# NewGateway.net
KiCad netlist of a schematic drawn in Altium Designer
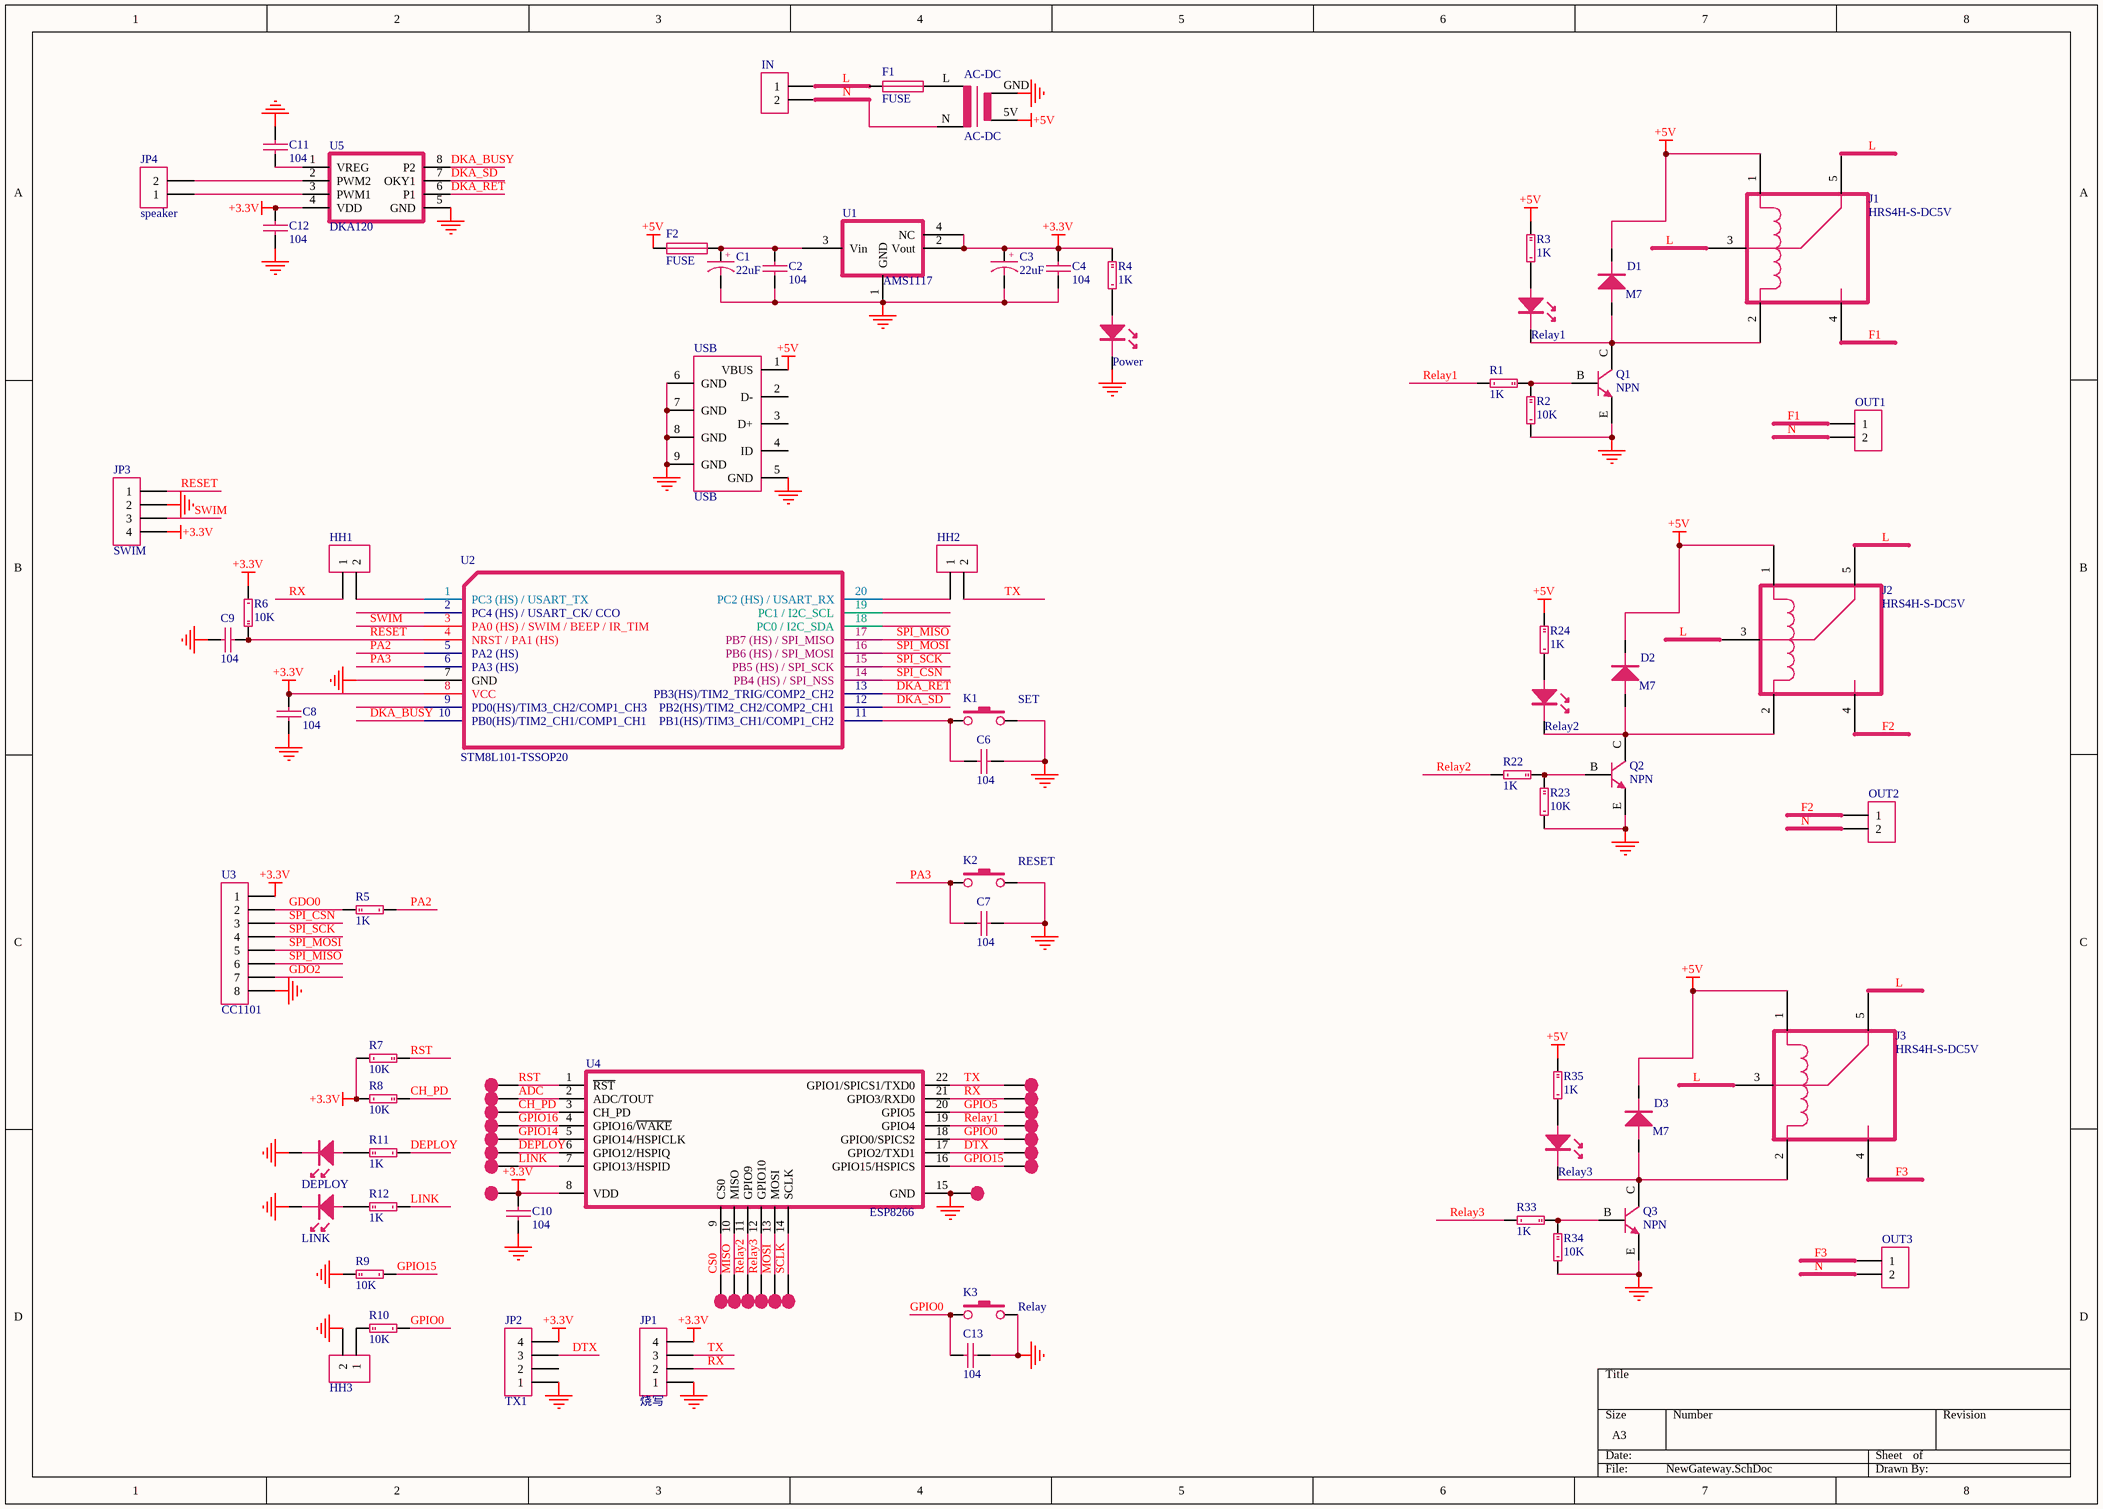
[diagram p0: NewGateway.SchDoc]

(export (version "E")
  (design (tool "Eeschema 10.0.6"))
  (components
    (comp (ref "AC-DC")
      (value "AC-DC")
      (footprint "AC-DC")
      (description "5V700mA(3.5W) 隔离开关电源模块/AC-DC降压模块")
      (libsource (lib "Sch_Lib") (part "AC-DC"))
    )
    (comp (ref "C1")
      (value "22uF")
      (footprint "C3528")
      (description "极性电容")
      (libsource (lib "Sch_Lib") (part "CAPACITOR"))
    )
    (comp (ref "C2")
      (value "104")
      (footprint "C0603")
      (description "无极性电容")
      (libsource (lib "Sch_Lib") (part "CAP"))
    )
    (comp (ref "C3")
      (value "22uF")
      (footprint "C3528")
      (description "极性电容")
      (libsource (lib "Sch_Lib") (part "CAPACITOR"))
    )
    (comp (ref "C4")
      (value "104")
      (footprint "C0603")
      (description "无极性电容")
      (libsource (lib "Sch_Lib") (part "CAP"))
    )
    (comp (ref "C6")
      (value "104")
      (footprint "C0603")
      (description "无极性电容")
      (libsource (lib "Sch_Lib") (part "CAP"))
    )
    (comp (ref "C7")
      (value "104")
      (footprint "C0603")
      (description "无极性电容")
      (libsource (lib "Sch_Lib") (part "CAP"))
    )
    (comp (ref "C8")
      (value "104")
      (footprint "C0603")
      (description "无极性电容")
      (libsource (lib "Sch_Lib") (part "CAP"))
    )
    (comp (ref "C9")
      (value "104")
      (footprint "C0603")
      (description "无极性电容")
      (libsource (lib "Sch_Lib") (part "CAP"))
    )
    (comp (ref "C10")
      (value "104")
      (footprint "C0603")
      (description "无极性电容")
      (libsource (lib "Sch_Lib") (part "CAP"))
    )
    (comp (ref "C11")
      (value "104")
      (footprint "C0603")
      (description "无极性电容")
      (libsource (lib "Sch_Lib") (part "CAP"))
    )
    (comp (ref "C12")
      (value "104")
      (footprint "C0603")
      (description "无极性电容")
      (libsource (lib "Sch_Lib") (part "CAP"))
    )
    (comp (ref "C13")
      (value "104")
      (footprint "C0603")
      (description "无极性电容")
      (libsource (lib "Sch_Lib") (part "CAP"))
    )
    (comp (ref "D1")
      (value "M7")
      (footprint "DO-214A")
      (description "二极管")
      (libsource (lib "Sch_Lib") (part "DIODE"))
    )
    (comp (ref "D2")
      (value "M7")
      (footprint "DO-214A")
      (description "二极管")
      (libsource (lib "Sch_Lib") (part "DIODE"))
    )
    (comp (ref "D3")
      (value "M7")
      (footprint "DO-214A")
      (description "二极管")
      (libsource (lib "Sch_Lib") (part "DIODE"))
    )
    (comp (ref "DEPLOY")
      (value "LED")
      (footprint "LED0603")
      (description "LED灯")
      (libsource (lib "Sch_Lib") (part "LED"))
    )
    (comp (ref "F1")
      (value "FUSE")
      (footprint "Fuse Holder")
      (description "保险丝")
      (libsource (lib "Sch_Lib") (part "FUSE"))
    )
    (comp (ref "F2")
      (value "FUSE")
      (footprint "F1208")
      (description "保险丝")
      (libsource (lib "Sch_Lib") (part "FUSE"))
    )
    (comp (ref "HH1")
      (value "~")
      (footprint "SIP2-2.54MM")
      (description "2P接插件")
      (libsource (lib "Sch_Lib") (part "HEADER 2X1"))
    )
    (comp (ref "HH2")
      (value "~")
      (footprint "SIP2-2.54MM")
      (description "2P接插件")
      (libsource (lib "Sch_Lib") (part "HEADER 2X1"))
    )
    (comp (ref "HH3")
      (value "~")
      (footprint "SIP2-2.54MM")
      (description "2P接插件")
      (libsource (lib "") (part "HEADER 2X1_1"))
    )
    (comp (ref "IN")
      (value "~")
      (footprint "2EDG_5.08_2P")
      (description "2P接插件")
      (libsource (lib "") (part "HEADER 2X1_1"))
    )
    (comp (ref "J1")
      (value "HRS4H-S-DC5V")
      (footprint "HRS4H")
      (description "HKE汇港继电器")
      (libsource (lib "Sch_Lib") (part "HRS4H-S-DC5V"))
    )
    (comp (ref "J2")
      (value "HRS4H-S-DC5V")
      (footprint "HRS4H")
      (description "HKE汇港继电器")
      (libsource (lib "Sch_Lib") (part "HRS4H-S-DC5V"))
    )
    (comp (ref "J3")
      (value "HRS4H-S-DC5V")
      (footprint "HRS4H")
      (description "HKE汇港继电器")
      (libsource (lib "Sch_Lib") (part "HRS4H-S-DC5V"))
    )
    (comp (ref "JP1")
      (value "烧写")
      (footprint "SIP4-2.54MM")
      (description "4P接插件")
      (libsource (lib "Sch_Lib") (part "HEADER 4X1"))
    )
    (comp (ref "JP2")
      (value "TX1")
      (footprint "SIP4-2.54MM")
      (description "4P接插件")
      (libsource (lib "Sch_Lib") (part "HEADER 4X1"))
    )
    (comp (ref "JP3")
      (value "SWIM")
      (footprint "SIP4-2.54MM")
      (description "4P接插件")
      (libsource (lib "") (part "HEADER 4X1_1"))
    )
    (comp (ref "JP4")
      (value "speaker")
      (footprint "SIP2-1.27MM")
      (description "2P接插件")
      (libsource (lib "") (part "HEADER 2X1_3"))
    )
    (comp (ref "K1")
      (value "SET")
      (footprint "SW-TACT-4.5MM")
      (description "按键")
      (libsource (lib "Sch_Lib") (part "SW-PB"))
    )
    (comp (ref "K2")
      (value "RESET")
      (footprint "SW-TACT-4.5MM")
      (description "按键")
      (libsource (lib "Sch_Lib") (part "SW-PB"))
    )
    (comp (ref "K3")
      (value "Relay")
      (footprint "SW-TACT-4.5MM")
      (description "按键")
      (libsource (lib "Sch_Lib") (part "SW-PB"))
    )
    (comp (ref "LINK")
      (value "LED")
      (footprint "LED0603")
      (description "LED灯")
      (libsource (lib "Sch_Lib") (part "LED"))
    )
    (comp (ref "OUT1")
      (value "~")
      (footprint "2EDG_5.08_2P")
      (description "2P接插件")
      (libsource (lib "") (part "HEADER 2X1_2"))
    )
    (comp (ref "OUT2")
      (value "~")
      (footprint "2EDG_5.08_2P")
      (description "2P接插件")
      (libsource (lib "") (part "HEADER 2X1_2"))
    )
    (comp (ref "OUT3")
      (value "~")
      (footprint "2EDG_5.08_2P")
      (description "2P接插件")
      (libsource (lib "") (part "HEADER 2X1_2"))
    )
    (comp (ref "Power")
      (value "LED")
      (footprint "LED0603")
      (description "LED灯")
      (libsource (lib "Sch_Lib") (part "LED"))
    )
    (comp (ref "Q1")
      (value "NPN")
      (footprint "SOT23")
      (description "NPN三极管")
      (fields (field (name "PUBLISHER") "*"))
      (libsource (lib "Sch_Lib") (part "NPN"))
    )
    (comp (ref "Q2")
      (value "NPN")
      (footprint "SOT23")
      (description "NPN三极管")
      (fields (field (name "PUBLISHER") "*"))
      (libsource (lib "Sch_Lib") (part "NPN"))
    )
    (comp (ref "Q3")
      (value "NPN")
      (footprint "SOT23")
      (description "NPN三极管")
      (fields (field (name "PUBLISHER") "*"))
      (libsource (lib "Sch_Lib") (part "NPN"))
    )
    (comp (ref "R1")
      (value "1K")
      (footprint "R0603")
      (description "贴片电阻")
      (libsource (lib "Sch_Lib") (part "RES2"))
    )
    (comp (ref "R2")
      (value "10K")
      (footprint "R0603")
      (description "贴片电阻")
      (libsource (lib "Sch_Lib") (part "RES2"))
    )
    (comp (ref "R3")
      (value "1K")
      (footprint "R0603")
      (description "贴片电阻")
      (libsource (lib "Sch_Lib") (part "RES2"))
    )
    (comp (ref "R4")
      (value "1K")
      (footprint "R0603")
      (description "贴片电阻")
      (libsource (lib "Sch_Lib") (part "RES2"))
    )
    (comp (ref "R5")
      (value "1K")
      (footprint "R0603")
      (description "贴片电阻")
      (libsource (lib "Sch_Lib") (part "RES2"))
    )
    (comp (ref "R6")
      (value "10K")
      (footprint "R0603")
      (description "贴片电阻")
      (libsource (lib "Sch_Lib") (part "RES2"))
    )
    (comp (ref "R7")
      (value "10K")
      (footprint "R0603")
      (description "贴片电阻")
      (libsource (lib "Sch_Lib") (part "RES2"))
    )
    (comp (ref "R8")
      (value "10K")
      (footprint "R0603")
      (description "贴片电阻")
      (libsource (lib "Sch_Lib") (part "RES2"))
    )
    (comp (ref "R9")
      (value "10K")
      (footprint "R0603")
      (description "贴片电阻")
      (libsource (lib "Sch_Lib") (part "RES2"))
    )
    (comp (ref "R10")
      (value "10K")
      (footprint "R0603")
      (description "贴片电阻")
      (libsource (lib "Sch_Lib") (part "RES2"))
    )
    (comp (ref "R11")
      (value "1K")
      (footprint "R0603")
      (description "贴片电阻")
      (libsource (lib "Sch_Lib") (part "RES2"))
    )
    (comp (ref "R12")
      (value "1K")
      (footprint "R0603")
      (description "贴片电阻")
      (libsource (lib "Sch_Lib") (part "RES2"))
    )
    (comp (ref "R22")
      (value "1K")
      (footprint "R0603")
      (description "贴片电阻")
      (libsource (lib "Sch_Lib") (part "RES2"))
    )
    (comp (ref "R23")
      (value "10K")
      (footprint "R0603")
      (description "贴片电阻")
      (libsource (lib "Sch_Lib") (part "RES2"))
    )
    (comp (ref "R24")
      (value "1K")
      (footprint "R0603")
      (description "贴片电阻")
      (libsource (lib "Sch_Lib") (part "RES2"))
    )
    (comp (ref "R33")
      (value "1K")
      (footprint "R0603")
      (description "贴片电阻")
      (libsource (lib "Sch_Lib") (part "RES2"))
    )
    (comp (ref "R34")
      (value "10K")
      (footprint "R0603")
      (description "贴片电阻")
      (libsource (lib "Sch_Lib") (part "RES2"))
    )
    (comp (ref "R35")
      (value "1K")
      (footprint "R0603")
      (description "贴片电阻")
      (libsource (lib "Sch_Lib") (part "RES2"))
    )
    (comp (ref "Relay1")
      (value "LED")
      (footprint "LED0603")
      (description "LED灯")
      (libsource (lib "Sch_Lib") (part "LED"))
    )
    (comp (ref "Relay2")
      (value "LED")
      (footprint "LED0603")
      (description "LED灯")
      (libsource (lib "Sch_Lib") (part "LED"))
    )
    (comp (ref "Relay3")
      (value "LED")
      (footprint "LED0603")
      (description "LED灯")
      (libsource (lib "Sch_Lib") (part "LED"))
    )
    (comp (ref "T1")
      (value "~")
      (footprint "TP")
      (description "测试点/触摸点")
      (libsource (lib "Sch_Lib") (part "TP"))
    )
    (comp (ref "T2")
      (value "~")
      (footprint "TP")
      (description "测试点/触摸点")
      (libsource (lib "Sch_Lib") (part "TP"))
    )
    (comp (ref "T3")
      (value "~")
      (footprint "TP")
      (description "测试点/触摸点")
      (libsource (lib "Sch_Lib") (part "TP"))
    )
    (comp (ref "T4")
      (value "~")
      (footprint "TP")
      (description "测试点/触摸点")
      (libsource (lib "Sch_Lib") (part "TP"))
    )
    (comp (ref "T5")
      (value "~")
      (footprint "TP")
      (description "测试点/触摸点")
      (libsource (lib "Sch_Lib") (part "TP"))
    )
    (comp (ref "T6")
      (value "~")
      (footprint "TP")
      (description "测试点/触摸点")
      (libsource (lib "Sch_Lib") (part "TP"))
    )
    (comp (ref "T7")
      (value "~")
      (footprint "TP")
      (description "测试点/触摸点")
      (libsource (lib "Sch_Lib") (part "TP"))
    )
    (comp (ref "T8")
      (value "~")
      (footprint "TP")
      (description "测试点/触摸点")
      (libsource (lib "Sch_Lib") (part "TP"))
    )
    (comp (ref "T9")
      (value "~")
      (footprint "TP")
      (description "测试点/触摸点")
      (libsource (lib "Sch_Lib") (part "TP"))
    )
    (comp (ref "T10")
      (value "~")
      (footprint "TP")
      (description "测试点/触摸点")
      (libsource (lib "Sch_Lib") (part "TP"))
    )
    (comp (ref "T11")
      (value "~")
      (footprint "TP")
      (description "测试点/触摸点")
      (libsource (lib "Sch_Lib") (part "TP"))
    )
    (comp (ref "T12")
      (value "~")
      (footprint "TP")
      (description "测试点/触摸点")
      (libsource (lib "Sch_Lib") (part "TP"))
    )
    (comp (ref "T13")
      (value "~")
      (footprint "TP")
      (description "测试点/触摸点")
      (libsource (lib "Sch_Lib") (part "TP"))
    )
    (comp (ref "T14")
      (value "~")
      (footprint "TP")
      (description "测试点/触摸点")
      (libsource (lib "Sch_Lib") (part "TP"))
    )
    (comp (ref "T15")
      (value "~")
      (footprint "TP")
      (description "测试点/触摸点")
      (libsource (lib "Sch_Lib") (part "TP"))
    )
    (comp (ref "T16")
      (value "~")
      (footprint "TP")
      (description "测试点/触摸点")
      (libsource (lib "Sch_Lib") (part "TP"))
    )
    (comp (ref "T17")
      (value "~")
      (footprint "TP")
      (description "测试点/触摸点")
      (libsource (lib "Sch_Lib") (part "TP"))
    )
    (comp (ref "T18")
      (value "~")
      (footprint "TP")
      (description "测试点/触摸点")
      (libsource (lib "Sch_Lib") (part "TP"))
    )
    (comp (ref "T19")
      (value "~")
      (footprint "TP")
      (description "测试点/触摸点")
      (libsource (lib "Sch_Lib") (part "TP"))
    )
    (comp (ref "T20")
      (value "~")
      (footprint "TP")
      (description "测试点/触摸点")
      (libsource (lib "Sch_Lib") (part "TP"))
    )
    (comp (ref "T21")
      (value "~")
      (footprint "TP")
      (description "测试点/触摸点")
      (libsource (lib "Sch_Lib") (part "TP"))
    )
    (comp (ref "T22")
      (value "~")
      (footprint "TP")
      (description "测试点/触摸点")
      (libsource (lib "Sch_Lib") (part "TP"))
    )
    (comp (ref "U1")
      (value "AMS1117")
      (footprint "SOT223")
      (description "稳压芯片(LDO)")
      (libsource (lib "Sch_Lib") (part "AMS1117"))
    )
    (comp (ref "U2")
      (value "STM8L101-TSSOP20")
      (footprint "TSSOP20")
      (description "STM8单片机20引脚")
      (libsource (lib "Sch_Lib") (part "STM8L101-TSSOP20"))
    )
    (comp (ref "U3")
      (value "CC1101")
      (footprint "CC1101S")
      (description "8P接插件")
      (libsource (lib "Sch_Lib") (part "HEADER 8X1"))
    )
    (comp (ref "U4")
      (value "ESP8266")
      (footprint "ESP-12E")
      (description "ESP8266贴片模块12E-F")
      (libsource (lib "Sch_Lib") (part "ESP8266-12E"))
    )
    (comp (ref "U5")
      (value "DKA120")
      (footprint "SOIC8")
      (description "语音芯片http://www.dk1699.com/")
      (libsource (lib "Sch_Lib") (part "DKA120"))
    )
    (comp (ref "USB")
      (value "USB")
      (footprint "USB-Micro")
      (description "通用串行总线(USB)")
      (libsource (lib "Sch_Lib") (part "USB"))
    )
  )
  (nets
    (net (code "1") (name "+3.3V") (class "Default")
      (node (ref "C10") (pin "1") (pinfunction "1_1") (pintype "passive"))
      (node (ref "C12") (pin "1") (pinfunction "1_1") (pintype "passive"))
      (node (ref "C3") (pin "1") (pinfunction "1_1") (pintype "passive"))
      (node (ref "C4") (pin "1") (pinfunction "1_1") (pintype "passive"))
      (node (ref "C8") (pin "2") (pinfunction "2_2") (pintype "passive"))
      (node (ref "JP1") (pin "4") (pinfunction "4_4") (pintype "passive"))
      (node (ref "JP2") (pin "4") (pinfunction "4_4") (pintype "passive"))
      (node (ref "JP3") (pin "4") (pinfunction "4_4") (pintype "passive"))
      (node (ref "R4") (pin "2") (pinfunction "2_2") (pintype "passive"))
      (node (ref "R6") (pin "1") (pinfunction "1_1") (pintype "passive"))
      (node (ref "R7") (pin "1") (pinfunction "1_1") (pintype "passive"))
      (node (ref "R8") (pin "1") (pinfunction "1_1") (pintype "passive"))
      (node (ref "T15") (pin "1") (pinfunction "1_1") (pintype "passive"))
      (node (ref "U1") (pin "2") (pinfunction "Vout_2") (pintype "passive"))
      (node (ref "U1") (pin "4") (pinfunction "NC_4") (pintype "passive"))
      (node (ref "U2") (pin "8") (pinfunction "VCC_8") (pintype "passive"))
      (node (ref "U3") (pin "1") (pinfunction "1_1") (pintype "passive"))
      (node (ref "U4") (pin "8") (pinfunction "VDD_8") (pintype "passive"))
      (node (ref "U5") (pin "4") (pinfunction "VDD_4") (pintype "passive"))
    )
    (net (code "2") (name "+5V") (class "Default")
      (node (ref "AC-DC") (pin "5V") (pinfunction "5V_5V") (pintype "passive"))
      (node (ref "D1") (pin "2") (pinfunction "2_2") (pintype "passive"))
      (node (ref "D2") (pin "2") (pinfunction "2_2") (pintype "passive"))
      (node (ref "D3") (pin "2") (pinfunction "2_2") (pintype "passive"))
      (node (ref "F2") (pin "1") (pinfunction "1_1") (pintype "passive"))
      (node (ref "J1") (pin "1") (pinfunction "1_1") (pintype "passive"))
      (node (ref "J2") (pin "1") (pinfunction "1_1") (pintype "passive"))
      (node (ref "J3") (pin "1") (pinfunction "1_1") (pintype "passive"))
      (node (ref "R24") (pin "2") (pinfunction "2_2") (pintype "passive"))
      (node (ref "R3") (pin "2") (pinfunction "2_2") (pintype "passive"))
      (node (ref "R35") (pin "2") (pinfunction "2_2") (pintype "passive"))
      (node (ref "USB") (pin "1") (pinfunction "VBUS_1") (pintype "passive"))
    )
    (net (code "3") (name "/ADC") (class "Default")
      (node (ref "T21") (pin "1") (pinfunction "1_1") (pintype "passive"))
      (node (ref "U4") (pin "2") (pinfunction "ADC/TOUT_2") (pintype "passive"))
    )
    (net (code "4") (name "/CH_PD") (class "Default")
      (node (ref "R8") (pin "2") (pinfunction "2_2") (pintype "passive"))
      (node (ref "T20") (pin "1") (pinfunction "1_1") (pintype "passive"))
      (node (ref "U4") (pin "3") (pinfunction "CH_PD_3") (pintype "passive"))
    )
    (net (code "5") (name "/CS0") (class "Default")
      (node (ref "T1") (pin "1") (pinfunction "1_1") (pintype "passive"))
      (node (ref "U4") (pin "9") (pinfunction "CS0_9") (pintype "passive"))
    )
    (net (code "6") (name "/DEPLOY") (class "Default")
      (node (ref "R11") (pin "1") (pinfunction "1_1") (pintype "passive"))
      (node (ref "T17") (pin "1") (pinfunction "1_1") (pintype "passive"))
      (node (ref "U4") (pin "6") (pinfunction "GPIO12/HSPIQ_6") (pintype "passive"))
    )
    (net (code "7") (name "/DKA_BUSY") (class "Default")
      (node (ref "U2") (pin "10") (pinfunction "PB0(HS)/TIM2_CH1/COMP1_CH1_10") (pintype "passive"))
      (node (ref "U5") (pin "8") (pinfunction "P2_8") (pintype "passive"))
    )
    (net (code "8") (name "/DKA_RET") (class "Default")
      (node (ref "U2") (pin "13") (pinfunction "PB3(HS)/TIM2_TRIG/COMP2_CH2_13") (pintype "passive"))
      (node (ref "U5") (pin "6") (pinfunction "P1_6") (pintype "passive"))
    )
    (net (code "9") (name "/DKA_SD") (class "Default")
      (node (ref "U2") (pin "12") (pinfunction "PB2(HS)/TIM2_CH2/COMP2_CH1_12") (pintype "passive"))
      (node (ref "U5") (pin "7") (pinfunction "OKY1_7") (pintype "passive"))
    )
    (net (code "10") (name "/DTX") (class "Default")
      (node (ref "JP2") (pin "3") (pinfunction "3_3") (pintype "passive"))
      (node (ref "T9") (pin "1") (pinfunction "1_1") (pintype "passive"))
      (node (ref "U4") (pin "17") (pinfunction "GPIO2/TXD1_17") (pintype "passive"))
    )
    (net (code "11") (name "/F1") (class "Default")
      (node (ref "J1") (pin "4") (pinfunction "4_4") (pintype "passive"))
      (node (ref "OUT1") (pin "1") (pinfunction "1_1") (pintype "passive"))
    )
    (net (code "12") (name "/F2") (class "Default")
      (node (ref "J2") (pin "4") (pinfunction "4_4") (pintype "passive"))
      (node (ref "OUT2") (pin "1") (pinfunction "1_1") (pintype "passive"))
    )
    (net (code "13") (name "/F3") (class "Default")
      (node (ref "J3") (pin "4") (pinfunction "4_4") (pintype "passive"))
      (node (ref "OUT3") (pin "1") (pinfunction "1_1") (pintype "passive"))
    )
    (net (code "14") (name "/GDO0") (class "Default")
      (node (ref "R5") (pin "2") (pinfunction "2_2") (pintype "passive"))
      (node (ref "U3") (pin "2") (pinfunction "2_2") (pintype "passive"))
    )
    (net (code "15") (name "/GDO2") (class "Default")
      (node (ref "U3") (pin "7") (pinfunction "7_7") (pintype "passive"))
    )
    (net (code "16") (name "/GPIO0") (class "Default")
      (node (ref "C13") (pin "1") (pinfunction "1_1") (pintype "passive"))
      (node (ref "K3") (pin "1") (pinfunction "1_1") (pintype "passive"))
      (node (ref "R10") (pin "1") (pinfunction "1_1") (pintype "passive"))
      (node (ref "T10") (pin "1") (pinfunction "1_1") (pintype "passive"))
      (node (ref "U4") (pin "18") (pinfunction "GPIO0/SPICS2_18") (pintype "passive"))
    )
    (net (code "17") (name "/GPIO5") (class "Default")
      (node (ref "T12") (pin "1") (pinfunction "1_1") (pintype "passive"))
      (node (ref "U4") (pin "20") (pinfunction "GPIO5_20") (pintype "passive"))
    )
    (net (code "18") (name "/GPIO14") (class "Default")
      (node (ref "T18") (pin "1") (pinfunction "1_1") (pintype "passive"))
      (node (ref "U4") (pin "5") (pinfunction "GPIO14/HSPICLK_5") (pintype "passive"))
    )
    (net (code "19") (name "/GPIO15") (class "Default")
      (node (ref "R9") (pin "1") (pinfunction "1_1") (pintype "passive"))
      (node (ref "T8") (pin "1") (pinfunction "1_1") (pintype "passive"))
      (node (ref "U4") (pin "16") (pinfunction "GPIO15/HSPICS_16") (pintype "passive"))
    )
    (net (code "20") (name "/GPIO16") (class "Default")
      (node (ref "T19") (pin "1") (pinfunction "1_1") (pintype "passive"))
      (node (ref "U4") (pin "4") (pinfunction "GPIO16/~{WAKE}_4") (pintype "passive"))
    )
    (net (code "21") (name "/L") (class "Default")
      (node (ref "F1") (pin "1") (pinfunction "1_1") (pintype "passive"))
      (node (ref "IN") (pin "1") (pinfunction "1_1") (pintype "passive"))
      (node (ref "J1") (pin "3") (pinfunction "3_3") (pintype "passive"))
      (node (ref "J1") (pin "5") (pinfunction "5_5") (pintype "passive"))
      (node (ref "J2") (pin "3") (pinfunction "3_3") (pintype "passive"))
      (node (ref "J2") (pin "5") (pinfunction "5_5") (pintype "passive"))
      (node (ref "J3") (pin "3") (pinfunction "3_3") (pintype "passive"))
      (node (ref "J3") (pin "5") (pinfunction "5_5") (pintype "passive"))
    )
    (net (code "22") (name "/LINK") (class "Default")
      (node (ref "R12") (pin "1") (pinfunction "1_1") (pintype "passive"))
      (node (ref "T16") (pin "1") (pinfunction "1_1") (pintype "passive"))
      (node (ref "U4") (pin "7") (pinfunction "GPIO13/HSPID_7") (pintype "passive"))
    )
    (net (code "23") (name "/MISO") (class "Default")
      (node (ref "T2") (pin "1") (pinfunction "1_1") (pintype "passive"))
      (node (ref "U4") (pin "10") (pinfunction "MISO_10") (pintype "passive"))
    )
    (net (code "24") (name "/MOSI") (class "Default")
      (node (ref "T5") (pin "1") (pinfunction "1_1") (pintype "passive"))
      (node (ref "U4") (pin "13") (pinfunction "MOSI_13") (pintype "passive"))
    )
    (net (code "25") (name "/N") (class "Default")
      (node (ref "AC-DC") (pin "N") (pinfunction "N_N") (pintype "passive"))
      (node (ref "IN") (pin "2") (pinfunction "2_2") (pintype "passive"))
      (node (ref "OUT1") (pin "2") (pinfunction "2_2") (pintype "passive"))
      (node (ref "OUT2") (pin "2") (pinfunction "2_2") (pintype "passive"))
      (node (ref "OUT3") (pin "2") (pinfunction "2_2") (pintype "passive"))
    )
    (net (code "26") (name "/PA2") (class "Default")
      (node (ref "R5") (pin "1") (pinfunction "1_1") (pintype "passive"))
      (node (ref "U2") (pin "5") (pinfunction "PA2_(HS)_5") (pintype "passive"))
    )
    (net (code "27") (name "/PA3") (class "Default")
      (node (ref "C7") (pin "1") (pinfunction "1_1") (pintype "passive"))
      (node (ref "K2") (pin "1") (pinfunction "1_1") (pintype "passive"))
      (node (ref "U2") (pin "6") (pinfunction "PA3_(HS)_6") (pintype "passive"))
    )
    (net (code "28") (name "/RESET") (class "Default")
      (node (ref "C9") (pin "1") (pinfunction "1_1") (pintype "passive"))
      (node (ref "JP3") (pin "1") (pinfunction "1_1") (pintype "passive"))
      (node (ref "R6") (pin "2") (pinfunction "2_2") (pintype "passive"))
      (node (ref "U2") (pin "4") (pinfunction "NRST_/_PA1_(HS)_4") (pintype "passive"))
    )
    (net (code "29") (name "/RST") (class "Default")
      (node (ref "R7") (pin "2") (pinfunction "2_2") (pintype "passive"))
      (node (ref "T22") (pin "1") (pinfunction "1_1") (pintype "passive"))
      (node (ref "U4") (pin "1") (pinfunction "~{RST}_1") (pintype "passive"))
    )
    (net (code "30") (name "/RX") (class "Default")
      (node (ref "HH1") (pin "1") (pinfunction "1_1") (pintype "passive"))
      (node (ref "JP1") (pin "2") (pinfunction "2_2") (pintype "passive"))
      (node (ref "T13") (pin "1") (pinfunction "1_1") (pintype "passive"))
      (node (ref "U4") (pin "21") (pinfunction "GPIO3/RXD0_21") (pintype "passive"))
    )
    (net (code "31") (name "/Relay1") (class "Default")
      (node (ref "R1") (pin "1") (pinfunction "1_1") (pintype "passive"))
      (node (ref "T11") (pin "1") (pinfunction "1_1") (pintype "passive"))
      (node (ref "U4") (pin "19") (pinfunction "GPIO4_19") (pintype "passive"))
    )
    (net (code "32") (name "/Relay2") (class "Default")
      (node (ref "R22") (pin "1") (pinfunction "1_1") (pintype "passive"))
      (node (ref "T3") (pin "1") (pinfunction "1_1") (pintype "passive"))
      (node (ref "U4") (pin "11") (pinfunction "GPIO9_11") (pintype "passive"))
    )
    (net (code "33") (name "/Relay3") (class "Default")
      (node (ref "R33") (pin "1") (pinfunction "1_1") (pintype "passive"))
      (node (ref "T4") (pin "1") (pinfunction "1_1") (pintype "passive"))
      (node (ref "U4") (pin "12") (pinfunction "GPIO10_12") (pintype "passive"))
    )
    (net (code "34") (name "/SCLK") (class "Default")
      (node (ref "T6") (pin "1") (pinfunction "1_1") (pintype "passive"))
      (node (ref "U4") (pin "14") (pinfunction "SCLK_14") (pintype "passive"))
    )
    (net (code "35") (name "/SPI_CSN") (class "Default")
      (node (ref "U2") (pin "14") (pinfunction "PB4_(HS)_/_SPI_NSS_14") (pintype "passive"))
      (node (ref "U3") (pin "3") (pinfunction "3_3") (pintype "passive"))
    )
    (net (code "36") (name "/SPI_MISO") (class "Default")
      (node (ref "U2") (pin "17") (pinfunction "PB7_(HS)_/_SPI_MISO_17") (pintype "passive"))
      (node (ref "U3") (pin "6") (pinfunction "6_6") (pintype "passive"))
    )
    (net (code "37") (name "/SPI_MOSI") (class "Default")
      (node (ref "U2") (pin "16") (pinfunction "PB6_(HS)_/_SPI_MOSI_16") (pintype "passive"))
      (node (ref "U3") (pin "5") (pinfunction "5_5") (pintype "passive"))
    )
    (net (code "38") (name "/SPI_SCK") (class "Default")
      (node (ref "U2") (pin "15") (pinfunction "PB5_(HS)_/_SPI_SCK_15") (pintype "passive"))
      (node (ref "U3") (pin "4") (pinfunction "4_4") (pintype "passive"))
    )
    (net (code "39") (name "/SWIM") (class "Default")
      (node (ref "JP3") (pin "3") (pinfunction "3_3") (pintype "passive"))
      (node (ref "U2") (pin "3") (pinfunction "PA0_(HS)_/_SWIM_/_BEEP_/_IR_TIM_3") (pintype "passive"))
    )
    (net (code "40") (name "/TX") (class "Default")
      (node (ref "HH2") (pin "2") (pinfunction "2_2") (pintype "passive"))
      (node (ref "JP1") (pin "3") (pinfunction "3_3") (pintype "passive"))
      (node (ref "T14") (pin "1") (pinfunction "1_1") (pintype "passive"))
      (node (ref "U4") (pin "22") (pinfunction "GPIO1/SPICS1/TXD0_22") (pintype "passive"))
    )
    (net (code "41") (name "GND") (class "Default")
      (node (ref "AC-DC") (pin "GND") (pinfunction "GND_GND") (pintype "passive"))
      (node (ref "C1") (pin "2") (pinfunction "2_2") (pintype "passive"))
      (node (ref "C10") (pin "2") (pinfunction "2_2") (pintype "passive"))
      (node (ref "C11") (pin "1") (pinfunction "1_1") (pintype "passive"))
      (node (ref "C12") (pin "2") (pinfunction "2_2") (pintype "passive"))
      (node (ref "C13") (pin "2") (pinfunction "2_2") (pintype "passive"))
      (node (ref "C2") (pin "2") (pinfunction "2_2") (pintype "passive"))
      (node (ref "C3") (pin "2") (pinfunction "2_2") (pintype "passive"))
      (node (ref "C4") (pin "2") (pinfunction "2_2") (pintype "passive"))
      (node (ref "C6") (pin "2") (pinfunction "2_2") (pintype "passive"))
      (node (ref "C7") (pin "2") (pinfunction "2_2") (pintype "passive"))
      (node (ref "C8") (pin "1") (pinfunction "1_1") (pintype "passive"))
      (node (ref "C9") (pin "2") (pinfunction "2_2") (pintype "passive"))
      (node (ref "DEPLOY") (pin "2") (pinfunction "2_2") (pintype "passive"))
      (node (ref "HH3") (pin "2") (pinfunction "2_2") (pintype "passive"))
      (node (ref "JP1") (pin "1") (pinfunction "1_1") (pintype "passive"))
      (node (ref "JP2") (pin "1") (pinfunction "1_1") (pintype "passive"))
      (node (ref "JP3") (pin "2") (pinfunction "2_2") (pintype "passive"))
      (node (ref "K1") (pin "2") (pinfunction "2_2") (pintype "passive"))
      (node (ref "K2") (pin "2") (pinfunction "2_2") (pintype "passive"))
      (node (ref "K3") (pin "2") (pinfunction "2_2") (pintype "passive"))
      (node (ref "LINK") (pin "2") (pinfunction "2_2") (pintype "passive"))
      (node (ref "Power") (pin "2") (pinfunction "2_2") (pintype "passive"))
      (node (ref "Q1") (pin "E") (pinfunction "E_E") (pintype "passive"))
      (node (ref "Q2") (pin "E") (pinfunction "E_E") (pintype "passive"))
      (node (ref "Q3") (pin "E") (pinfunction "E_E") (pintype "passive"))
      (node (ref "R2") (pin "1") (pinfunction "1_1") (pintype "passive"))
      (node (ref "R23") (pin "1") (pinfunction "1_1") (pintype "passive"))
      (node (ref "R34") (pin "1") (pinfunction "1_1") (pintype "passive"))
      (node (ref "R9") (pin "2") (pinfunction "2_2") (pintype "passive"))
      (node (ref "T7") (pin "1") (pinfunction "1_1") (pintype "passive"))
      (node (ref "U1") (pin "1") (pinfunction "GND_1") (pintype "passive"))
      (node (ref "U2") (pin "7") (pinfunction "GND_7") (pintype "passive"))
      (node (ref "U3") (pin "8") (pinfunction "8_8") (pintype "passive"))
      (node (ref "U4") (pin "15") (pinfunction "GND_15") (pintype "passive"))
      (node (ref "U5") (pin "5") (pinfunction "GND_5") (pintype "passive"))
      (node (ref "USB") (pin "5") (pinfunction "GND_5") (pintype "passive"))
      (node (ref "USB") (pin "6") (pinfunction "GND_6") (pintype "power_in"))
      (node (ref "USB") (pin "7") (pinfunction "GND_7") (pintype "power_in"))
      (node (ref "USB") (pin "8") (pinfunction "GND_8") (pintype "power_in"))
      (node (ref "USB") (pin "9") (pinfunction "GND_9") (pintype "power_in"))
    )
    (net (code "42") (name "Net-(AC-DC-PadL)") (class "Default")
      (node (ref "AC-DC") (pin "L") (pinfunction "L_L") (pintype "passive"))
      (node (ref "F1") (pin "2") (pinfunction "2_2") (pintype "passive"))
    )
    (net (code "43") (name "Net-(D1-Pad1)") (class "Default")
      (node (ref "D1") (pin "1") (pinfunction "1_1") (pintype "passive"))
      (node (ref "J1") (pin "2") (pinfunction "2_2") (pintype "passive"))
      (node (ref "Q1") (pin "C") (pinfunction "C_C") (pintype "passive"))
      (node (ref "Relay1") (pin "2") (pinfunction "2_2") (pintype "passive"))
    )
    (net (code "44") (name "Net-(D2-Pad1)") (class "Default")
      (node (ref "D2") (pin "1") (pinfunction "1_1") (pintype "passive"))
      (node (ref "J2") (pin "2") (pinfunction "2_2") (pintype "passive"))
      (node (ref "Q2") (pin "C") (pinfunction "C_C") (pintype "passive"))
      (node (ref "Relay2") (pin "2") (pinfunction "2_2") (pintype "passive"))
    )
    (net (code "45") (name "Net-(D3-Pad1)") (class "Default")
      (node (ref "D3") (pin "1") (pinfunction "1_1") (pintype "passive"))
      (node (ref "J3") (pin "2") (pinfunction "2_2") (pintype "passive"))
      (node (ref "Q3") (pin "C") (pinfunction "C_C") (pintype "passive"))
      (node (ref "Relay3") (pin "2") (pinfunction "2_2") (pintype "passive"))
    )
    (net (code "46") (name "Net-(DEPLOY-Pad1)") (class "Default")
      (node (ref "DEPLOY") (pin "1") (pinfunction "1_1") (pintype "passive"))
      (node (ref "R11") (pin "2") (pinfunction "2_2") (pintype "passive"))
    )
    (net (code "47") (name "Net-(HH3-Pad1)") (class "Default")
      (node (ref "HH3") (pin "1") (pinfunction "1_1") (pintype "passive"))
      (node (ref "R10") (pin "2") (pinfunction "2_2") (pintype "passive"))
    )
    (net (code "48") (name "Net-(LINK-Pad1)") (class "Default")
      (node (ref "LINK") (pin "1") (pinfunction "1_1") (pintype "passive"))
      (node (ref "R12") (pin "2") (pinfunction "2_2") (pintype "passive"))
    )
    (net (code "49") (name "Net-(Power-Pad1)") (class "Default")
      (node (ref "Power") (pin "1") (pinfunction "1_1") (pintype "passive"))
      (node (ref "R4") (pin "1") (pinfunction "1_1") (pintype "passive"))
    )
    (net (code "50") (name "Net-(Q1-PadB)") (class "Default")
      (node (ref "Q1") (pin "B") (pinfunction "B_B") (pintype "passive"))
      (node (ref "R1") (pin "2") (pinfunction "2_2") (pintype "passive"))
      (node (ref "R2") (pin "2") (pinfunction "2_2") (pintype "passive"))
    )
    (net (code "51") (name "Net-(Q2-PadB)") (class "Default")
      (node (ref "Q2") (pin "B") (pinfunction "B_B") (pintype "passive"))
      (node (ref "R22") (pin "2") (pinfunction "2_2") (pintype "passive"))
      (node (ref "R23") (pin "2") (pinfunction "2_2") (pintype "passive"))
    )
    (net (code "52") (name "Net-(Q3-PadB)") (class "Default")
      (node (ref "Q3") (pin "B") (pinfunction "B_B") (pintype "passive"))
      (node (ref "R33") (pin "2") (pinfunction "2_2") (pintype "passive"))
      (node (ref "R34") (pin "2") (pinfunction "2_2") (pintype "passive"))
    )
    (net (code "53") (name "Net-(R3-Pad1)") (class "Default")
      (node (ref "R3") (pin "1") (pinfunction "1_1") (pintype "passive"))
      (node (ref "Relay1") (pin "1") (pinfunction "1_1") (pintype "passive"))
    )
    (net (code "54") (name "Net-(R24-Pad1)") (class "Default")
      (node (ref "R24") (pin "1") (pinfunction "1_1") (pintype "passive"))
      (node (ref "Relay2") (pin "1") (pinfunction "1_1") (pintype "passive"))
    )
    (net (code "55") (name "Net-(R35-Pad1)") (class "Default")
      (node (ref "R35") (pin "1") (pinfunction "1_1") (pintype "passive"))
      (node (ref "Relay3") (pin "1") (pinfunction "1_1") (pintype "passive"))
    )
    (net (code "56") (name "Net-(U1-Vin)") (class "Default")
      (node (ref "C1") (pin "1") (pinfunction "1_1") (pintype "passive"))
      (node (ref "C2") (pin "1") (pinfunction "1_1") (pintype "passive"))
      (node (ref "F2") (pin "2") (pinfunction "2_2") (pintype "passive"))
      (node (ref "U1") (pin "3") (pinfunction "Vin_3") (pintype "passive"))
    )
    (net (code "57") (name "Net-(U2-PB1(HS){slash}TIM3_CH1{slash}COMP1_CH2)") (class "Default")
      (node (ref "C6") (pin "1") (pinfunction "1_1") (pintype "passive"))
      (node (ref "K1") (pin "1") (pinfunction "1_1") (pintype "passive"))
      (node (ref "U2") (pin "11") (pinfunction "PB1(HS)/TIM3_CH1/COMP1_CH2_11") (pintype "passive"))
    )
    (net (code "58") (name "Net-(U2-PC2_(HS)_{slash}_USART_RX)") (class "Default")
      (node (ref "HH2") (pin "1") (pinfunction "1_1") (pintype "passive"))
      (node (ref "U2") (pin "20") (pinfunction "PC2_(HS)_/_USART_RX_20") (pintype "passive"))
    )
    (net (code "59") (name "Net-(U2-PC3_(HS)_{slash}_USART_TX)") (class "Default")
      (node (ref "HH1") (pin "2") (pinfunction "2_2") (pintype "passive"))
      (node (ref "U2") (pin "1") (pinfunction "PC3_(HS)_/_USART_TX_1") (pintype "passive"))
    )
    (net (code "60") (name "Net-(U5-PWM1)") (class "Default")
      (node (ref "JP4") (pin "1") (pinfunction "1_1") (pintype "passive"))
      (node (ref "U5") (pin "3") (pinfunction "PWM1_3") (pintype "passive"))
    )
    (net (code "61") (name "Net-(U5-PWM2)") (class "Default")
      (node (ref "JP4") (pin "2") (pinfunction "2_2") (pintype "passive"))
      (node (ref "U5") (pin "2") (pinfunction "PWM2_2") (pintype "passive"))
    )
    (net (code "62") (name "Net-(U5-VREG)") (class "Default")
      (node (ref "C11") (pin "2") (pinfunction "2_2") (pintype "passive"))
      (node (ref "U5") (pin "1") (pinfunction "VREG_1") (pintype "passive"))
    )
    (net (code "63") (name "unconnected-(JP2-Pad2)") (class "Default")
      (node (ref "JP2") (pin "2") (pinfunction "2_2") (pintype "passive"))
    )
    (net (code "64") (name "unconnected-(U2-PC0_{slash}_I2C_SDA-Pad18)") (class "Default")
      (node (ref "U2") (pin "18") (pinfunction "PC0_/_I2C_SDA_18") (pintype "passive"))
    )
    (net (code "65") (name "unconnected-(U2-PC1_{slash}_I2C_SCL-Pad19)") (class "Default")
      (node (ref "U2") (pin "19") (pinfunction "PC1_/_I2C_SCL_19") (pintype "passive"))
    )
    (net (code "66") (name "unconnected-(U2-PC4_(HS)_{slash}_USART_CK{slash}_CCO-Pad2)") (class "Default")
      (node (ref "U2") (pin "2") (pinfunction "PC4_(HS)_/_USART_CK/_CCO_2") (pintype "passive"))
    )
    (net (code "67") (name "unconnected-(U2-PD0(HS){slash}TIM3_CH2{slash}COMP1_CH3-Pad9)") (class "Default")
      (node (ref "U2") (pin "9") (pinfunction "PD0(HS)/TIM3_CH2/COMP1_CH3_9") (pintype "passive"))
    )
    (net (code "68") (name "unconnected-(USB-D+-Pad3)") (class "Default")
      (node (ref "USB") (pin "3") (pinfunction "D+_3") (pintype "passive"))
    )
    (net (code "69") (name "unconnected-(USB-D--Pad2)") (class "Default")
      (node (ref "USB") (pin "2") (pinfunction "D-_2") (pintype "passive"))
    )
    (net (code "70") (name "unconnected-(USB-ID-Pad4)") (class "Default")
      (node (ref "USB") (pin "4") (pinfunction "ID_4") (pintype "passive"))
    )
  )
)
